# RobotCtrl_Core.net
KiCad netlist of a schematic drawn in Altium Designer
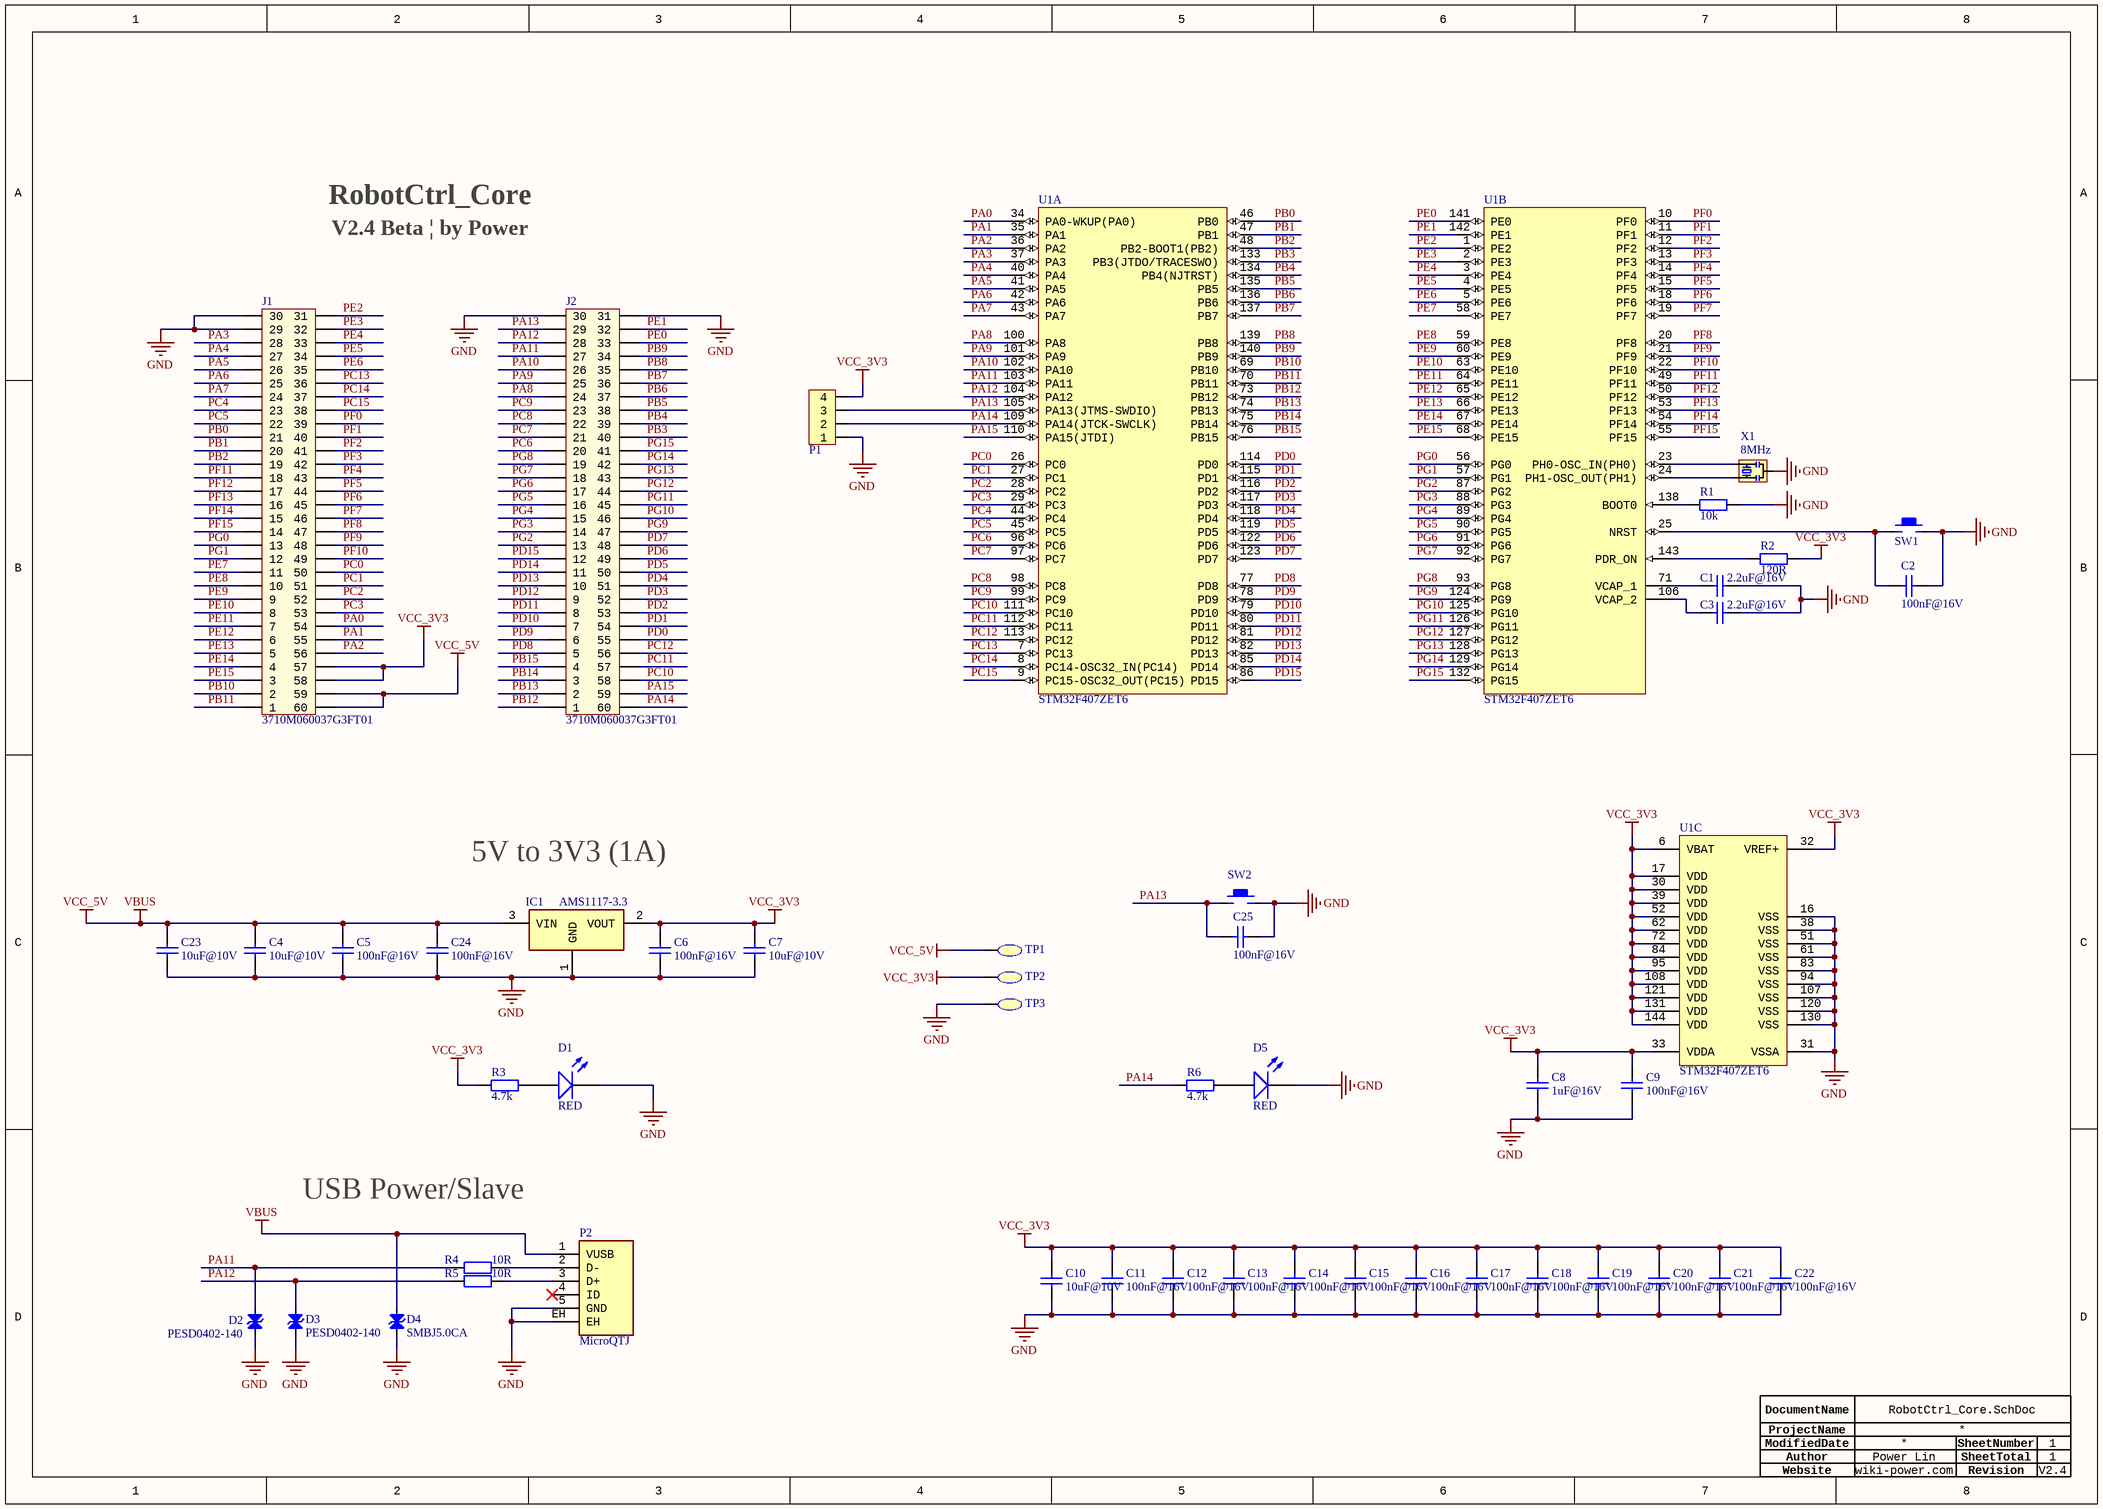
[diagram p0: RobotCtrl_Core.SchDoc]

(export (version "E")
  (design (tool "Eeschema 10.0.6"))
  (components
    (comp (ref "C1")
      (value "2.2uF@16V")
      (footprint "CAP-0402")
      (description "(CC0402KRX5R7BB225)")
      (libsource (lib "Power_Lib_Altium") (part "CAP"))
    )
    (comp (ref "C2")
      (value "100nF@16V")
      (footprint "CAP-0402")
      (description "(CC0402JRX7R7BB104)")
      (libsource (lib "Power_Lib_Altium") (part "CAP"))
    )
    (comp (ref "C3")
      (value "2.2uF@16V")
      (footprint "CAP-0402")
      (description "(CC0402KRX5R7BB225)")
      (libsource (lib "Power_Lib_Altium") (part "CAP"))
    )
    (comp (ref "C4")
      (value "10uF@10V")
      (footprint "CAP-0402")
      (description "(CC0402MRX5R6BB106)")
      (libsource (lib "Power_Lib_Altium") (part "CAP"))
    )
    (comp (ref "C5")
      (value "100nF@16V")
      (footprint "CAP-0402")
      (description "(CC0402JRX7R7BB104)")
      (libsource (lib "Power_Lib_Altium") (part "CAP"))
    )
    (comp (ref "C6")
      (value "100nF@16V")
      (footprint "CAP-0402")
      (description "(CC0402JRX7R7BB104)")
      (libsource (lib "Power_Lib_Altium") (part "CAP"))
    )
    (comp (ref "C7")
      (value "10uF@10V")
      (footprint "CAP-0402")
      (description "(CC0402MRX5R6BB106)")
      (libsource (lib "Power_Lib_Altium") (part "CAP"))
    )
    (comp (ref "C8")
      (value "1uF@16V")
      (footprint "CAP-0402")
      (description "(CC0402KRX5R7BB105)")
      (libsource (lib "Power_Lib_Altium") (part "CAP"))
    )
    (comp (ref "C9")
      (value "100nF@16V")
      (footprint "CAP-0402")
      (description "(CC0402JRX7R7BB104)")
      (libsource (lib "Power_Lib_Altium") (part "CAP"))
    )
    (comp (ref "C10")
      (value "10uF@10V")
      (footprint "CAP-0402")
      (description "(CC0402MRX5R6BB106)")
      (libsource (lib "Power_Lib_Altium") (part "CAP"))
    )
    (comp (ref "C11")
      (value "100nF@16V")
      (footprint "CAP-0402")
      (description "(CC0402JRX7R7BB104)")
      (libsource (lib "Power_Lib_Altium") (part "CAP"))
    )
    (comp (ref "C12")
      (value "100nF@16V")
      (footprint "CAP-0402")
      (description "(CC0402JRX7R7BB104)")
      (libsource (lib "Power_Lib_Altium") (part "CAP"))
    )
    (comp (ref "C13")
      (value "100nF@16V")
      (footprint "CAP-0402")
      (description "(CC0402JRX7R7BB104)")
      (libsource (lib "Power_Lib_Altium") (part "CAP"))
    )
    (comp (ref "C14")
      (value "100nF@16V")
      (footprint "CAP-0402")
      (description "(CC0402JRX7R7BB104)")
      (libsource (lib "Power_Lib_Altium") (part "CAP"))
    )
    (comp (ref "C15")
      (value "100nF@16V")
      (footprint "CAP-0402")
      (description "(CC0402JRX7R7BB104)")
      (libsource (lib "Power_Lib_Altium") (part "CAP"))
    )
    (comp (ref "C16")
      (value "100nF@16V")
      (footprint "CAP-0402")
      (description "(CC0402JRX7R7BB104)")
      (libsource (lib "Power_Lib_Altium") (part "CAP"))
    )
    (comp (ref "C17")
      (value "100nF@16V")
      (footprint "CAP-0402")
      (description "(CC0402JRX7R7BB104)")
      (libsource (lib "Power_Lib_Altium") (part "CAP"))
    )
    (comp (ref "C18")
      (value "100nF@16V")
      (footprint "CAP-0402")
      (description "(CC0402JRX7R7BB104)")
      (libsource (lib "Power_Lib_Altium") (part "CAP"))
    )
    (comp (ref "C19")
      (value "100nF@16V")
      (footprint "CAP-0402")
      (description "(CC0402JRX7R7BB104)")
      (libsource (lib "Power_Lib_Altium") (part "CAP"))
    )
    (comp (ref "C20")
      (value "100nF@16V")
      (footprint "CAP-0402")
      (description "(CC0402JRX7R7BB104)")
      (libsource (lib "Power_Lib_Altium") (part "CAP"))
    )
    (comp (ref "C21")
      (value "100nF@16V")
      (footprint "CAP-0402")
      (description "(CC0402JRX7R7BB104)")
      (libsource (lib "Power_Lib_Altium") (part "CAP"))
    )
    (comp (ref "C22")
      (value "100nF@16V")
      (footprint "CAP-0402")
      (description "(CC0402JRX7R7BB104)")
      (libsource (lib "Power_Lib_Altium") (part "CAP"))
    )
    (comp (ref "C23")
      (value "10uF@10V")
      (footprint "CAP-0402")
      (description "(CC0402MRX5R6BB106)")
      (libsource (lib "Power_Lib_Altium") (part "CAP"))
    )
    (comp (ref "C24")
      (value "100nF@16V")
      (footprint "CAP-0402")
      (description "(CC0402JRX7R7BB104)")
      (libsource (lib "Power_Lib_Altium") (part "CAP"))
    )
    (comp (ref "C25")
      (value "100nF@16V")
      (footprint "CAP-0402")
      (description "(CC0402JRX7R7BB104)")
      (libsource (lib "Power_Lib_Altium") (part "CAP"))
    )
    (comp (ref "D1")
      (value "RED")
      (footprint "LED-0402")
      (description "发光二极管")
      (libsource (lib "Power_Lib_Altium") (part "LED"))
    )
    (comp (ref "D2")
      (value "PESD0402-140")
      (footprint "D-0402")
      (libsource (lib "Power_Lib_Altium") (part "TVS_C"))
    )
    (comp (ref "D3")
      (value "PESD0402-140")
      (footprint "D-0402")
      (libsource (lib "Power_Lib_Altium") (part "TVS_C"))
    )
    (comp (ref "D4")
      (value "SMBJ5.0CA")
      (footprint "DO-214AA/SMB")
      (description "Brightking / MDD")
      (libsource (lib "Power_Lib_Altium") (part "TVS_C"))
    )
    (comp (ref "D5")
      (value "RED")
      (footprint "LED-0402")
      (description "发光二极管")
      (libsource (lib "Power_Lib_Altium") (part "LED"))
    )
    (comp (ref "IC1")
      (value "AMS1117-3.3")
      (footprint "SOT-223")
      (description "AMS1117-3.3 1.0A")
      (fields (field (name "MANUFACTURER_PART_NUMBER") "SI2302DS") (field (name "RS PART NUMBER") "7983053P"))
      (libsource (lib "Power_Lib_Altium") (part "AMS1117"))
    )
    (comp (ref "J1")
      (value "3710M060037G3FT01")
      (footprint "3710M060037G3FT01")
      (description "B2B Connector")
      (libsource (lib "Power_Lib_Altium") (part "3710M/F"))
    )
    (comp (ref "J2")
      (value "3710M060037G3FT01")
      (footprint "3710M060037G3FT01")
      (description "B2B Connector")
      (libsource (lib "Power_Lib_Altium") (part "3710M/F"))
    )
    (comp (ref "P1")
      (value "HDR1x4_2.54")
      (footprint "HDR1X4_2.54")
      (description "Header")
      (libsource (lib "Power_Lib_Altium") (part "HDR1x4_2.54"))
    )
    (comp (ref "P2")
      (value "MicroQTJ")
      (footprint "USB-MICRO")
      (description "USB_MICRO")
      (libsource (lib "Power_Lib_Altium") (part "USB_MICRO"))
    )
    (comp (ref "R1")
      (value "10k")
      (footprint "R-0402")
      (description "贴片电阻")
      (libsource (lib "") (part "RES_1"))
    )
    (comp (ref "R2")
      (value "120R")
      (footprint "R-0402")
      (description "贴片电阻")
      (libsource (lib "") (part "RES_1"))
    )
    (comp (ref "R3")
      (value "4.7k")
      (footprint "R-0402")
      (description "贴片电阻")
      (libsource (lib "") (part "RES_1"))
    )
    (comp (ref "R4")
      (value "10R")
      (footprint "R-0402")
      (description "贴片电阻")
      (libsource (lib "Power_Lib_Altium") (part "RES"))
    )
    (comp (ref "R5")
      (value "10R")
      (footprint "R-0402")
      (description "贴片电阻")
      (libsource (lib "Power_Lib_Altium") (part "RES"))
    )
    (comp (ref "R6")
      (value "4.7k")
      (footprint "R-0402")
      (description "贴片电阻")
      (libsource (lib "") (part "RES_1"))
    )
    (comp (ref "SW1")
      (value "KEY")
      (footprint "KEY-4P-4.2*3.4*2.5")
      (description "按键开关")
      (libsource (lib "Power_Lib_Altium") (part "KEY"))
    )
    (comp (ref "SW2")
      (value "KEY")
      (footprint "KEY-4P-4.2*3.4*2.5")
      (description "按键开关")
      (libsource (lib "Power_Lib_Altium") (part "KEY"))
    )
    (comp (ref "TP1")
      (value "TestPoint")
      (footprint "TestPoint")
      (description "测试点")
      (libsource (lib "Power_Lib_Altium") (part "TestPoint"))
    )
    (comp (ref "TP2")
      (value "TestPoint")
      (footprint "TestPoint")
      (description "测试点")
      (libsource (lib "Power_Lib_Altium") (part "TestPoint"))
    )
    (comp (ref "TP3")
      (value "TestPoint")
      (footprint "TestPoint")
      (description "测试点")
      (libsource (lib "Power_Lib_Altium") (part "TestPoint"))
    )
    (comp (ref "U1")
      (value "STM32F407ZET6")
      (footprint "STM-LQFP144_N")
      (fields (field (name "MANUFACTURER") "STMicroelectronics"))
      (libsource (lib "Power_Lib_Altium") (part "STM32F407ZET6"))
    )
    (comp (ref "X1")
      (value "8MHz")
      (footprint "SMD3213-3P")
      (description "CSTCE8M00G15C99-R0")
      (libsource (lib "Power_Lib_Altium") (part "XTAL"))
    )
  )
  (nets
    (net (code "1") (name "/PA0") (class "Default")
      (node (ref "J1") (pin "54") (pinfunction "54_54") (pintype "passive"))
      (node (ref "U1") (pin "34") (pinfunction "PA0-WKUP(PA0)_34") (pintype "bidirectional"))
    )
    (net (code "2") (name "/PA1") (class "Default")
      (node (ref "J1") (pin "55") (pinfunction "55_55") (pintype "passive"))
      (node (ref "U1") (pin "35") (pinfunction "PA1_35") (pintype "bidirectional"))
    )
    (net (code "3") (name "/PA2") (class "Default")
      (node (ref "J1") (pin "56") (pinfunction "56_56") (pintype "passive"))
      (node (ref "U1") (pin "36") (pinfunction "PA2_36") (pintype "bidirectional"))
    )
    (net (code "4") (name "/PA3") (class "Default")
      (node (ref "J1") (pin "28") (pinfunction "28_28") (pintype "passive"))
      (node (ref "U1") (pin "37") (pinfunction "PA3_37") (pintype "bidirectional"))
    )
    (net (code "5") (name "/PA4") (class "Default")
      (node (ref "J1") (pin "27") (pinfunction "27_27") (pintype "passive"))
      (node (ref "U1") (pin "40") (pinfunction "PA4_40") (pintype "bidirectional"))
    )
    (net (code "6") (name "/PA5") (class "Default")
      (node (ref "J1") (pin "26") (pinfunction "26_26") (pintype "passive"))
      (node (ref "U1") (pin "41") (pinfunction "PA5_41") (pintype "bidirectional"))
    )
    (net (code "7") (name "/PA6") (class "Default")
      (node (ref "J1") (pin "25") (pinfunction "25_25") (pintype "passive"))
      (node (ref "U1") (pin "42") (pinfunction "PA6_42") (pintype "bidirectional"))
    )
    (net (code "8") (name "/PA7") (class "Default")
      (node (ref "J1") (pin "24") (pinfunction "24_24") (pintype "passive"))
      (node (ref "U1") (pin "43") (pinfunction "PA7_43") (pintype "bidirectional"))
    )
    (net (code "9") (name "/PA8") (class "Default")
      (node (ref "J2") (pin "24") (pinfunction "24_24") (pintype "passive"))
      (node (ref "U1") (pin "100") (pinfunction "PA8_100") (pintype "bidirectional"))
    )
    (net (code "10") (name "/PA9") (class "Default")
      (node (ref "J2") (pin "25") (pinfunction "25_25") (pintype "passive"))
      (node (ref "U1") (pin "101") (pinfunction "PA9_101") (pintype "bidirectional"))
    )
    (net (code "11") (name "/PA10") (class "Default")
      (node (ref "J2") (pin "26") (pinfunction "26_26") (pintype "passive"))
      (node (ref "U1") (pin "102") (pinfunction "PA10_102") (pintype "bidirectional"))
    )
    (net (code "12") (name "/PA11") (class "Default")
      (node (ref "D2") (pin "2") (pinfunction "2_2") (pintype "passive"))
      (node (ref "J2") (pin "27") (pinfunction "27_27") (pintype "passive"))
      (node (ref "R4") (pin "1") (pinfunction "1_1") (pintype "passive"))
      (node (ref "U1") (pin "103") (pinfunction "PA11_103") (pintype "bidirectional"))
    )
    (net (code "13") (name "/PA12") (class "Default")
      (node (ref "D3") (pin "2") (pinfunction "2_2") (pintype "passive"))
      (node (ref "J2") (pin "28") (pinfunction "28_28") (pintype "passive"))
      (node (ref "R5") (pin "1") (pinfunction "1_1") (pintype "passive"))
      (node (ref "U1") (pin "104") (pinfunction "PA12_104") (pintype "bidirectional"))
    )
    (net (code "14") (name "/PA13") (class "Default")
      (node (ref "C25") (pin "2") (pinfunction "2_2") (pintype "passive"))
      (node (ref "J2") (pin "29") (pinfunction "29_29") (pintype "passive"))
      (node (ref "P1") (pin "3") (pinfunction "3_3") (pintype "passive"))
      (node (ref "SW2") (pin "1") (pinfunction "1_1") (pintype "passive"))
      (node (ref "U1") (pin "105") (pinfunction "PA13(JTMS-SWDIO)_105") (pintype "bidirectional"))
    )
    (net (code "15") (name "/PA14") (class "Default")
      (node (ref "J2") (pin "60") (pinfunction "60_60") (pintype "passive"))
      (node (ref "P1") (pin "2") (pinfunction "2_2") (pintype "passive"))
      (node (ref "R6") (pin "2") (pinfunction "2_2") (pintype "passive"))
      (node (ref "U1") (pin "109") (pinfunction "PA14(JTCK-SWCLK)_109") (pintype "bidirectional"))
    )
    (net (code "16") (name "/PA15") (class "Default")
      (node (ref "J2") (pin "59") (pinfunction "59_59") (pintype "passive"))
      (node (ref "U1") (pin "110") (pinfunction "PA15(JTDI)_110") (pintype "bidirectional"))
    )
    (net (code "17") (name "/PB0") (class "Default")
      (node (ref "J1") (pin "21") (pinfunction "21_21") (pintype "passive"))
      (node (ref "U1") (pin "46") (pinfunction "PB0_46") (pintype "bidirectional"))
    )
    (net (code "18") (name "/PB1") (class "Default")
      (node (ref "J1") (pin "20") (pinfunction "20_20") (pintype "passive"))
      (node (ref "U1") (pin "47") (pinfunction "PB1_47") (pintype "bidirectional"))
    )
    (net (code "19") (name "/PB2") (class "Default")
      (node (ref "J1") (pin "19") (pinfunction "19_19") (pintype "passive"))
      (node (ref "U1") (pin "48") (pinfunction "PB2-BOOT1(PB2)_48") (pintype "bidirectional"))
    )
    (net (code "20") (name "/PB3") (class "Default")
      (node (ref "J2") (pin "40") (pinfunction "40_40") (pintype "passive"))
      (node (ref "U1") (pin "133") (pinfunction "PB3(JTDO/TRACESWO)_133") (pintype "bidirectional"))
    )
    (net (code "21") (name "/PB4") (class "Default")
      (node (ref "J2") (pin "39") (pinfunction "39_39") (pintype "passive"))
      (node (ref "U1") (pin "134") (pinfunction "PB4(NJTRST)_134") (pintype "bidirectional"))
    )
    (net (code "22") (name "/PB5") (class "Default")
      (node (ref "J2") (pin "38") (pinfunction "38_38") (pintype "passive"))
      (node (ref "U1") (pin "135") (pinfunction "PB5_135") (pintype "bidirectional"))
    )
    (net (code "23") (name "/PB6") (class "Default")
      (node (ref "J2") (pin "37") (pinfunction "37_37") (pintype "passive"))
      (node (ref "U1") (pin "136") (pinfunction "PB6_136") (pintype "bidirectional"))
    )
    (net (code "24") (name "/PB7") (class "Default")
      (node (ref "J2") (pin "36") (pinfunction "36_36") (pintype "passive"))
      (node (ref "U1") (pin "137") (pinfunction "PB7_137") (pintype "bidirectional"))
    )
    (net (code "25") (name "/PB8") (class "Default")
      (node (ref "J2") (pin "35") (pinfunction "35_35") (pintype "passive"))
      (node (ref "U1") (pin "139") (pinfunction "PB8_139") (pintype "bidirectional"))
    )
    (net (code "26") (name "/PB9") (class "Default")
      (node (ref "J2") (pin "34") (pinfunction "34_34") (pintype "passive"))
      (node (ref "U1") (pin "140") (pinfunction "PB9_140") (pintype "bidirectional"))
    )
    (net (code "27") (name "/PB10") (class "Default")
      (node (ref "J1") (pin "2") (pinfunction "2_2") (pintype "passive"))
      (node (ref "U1") (pin "69") (pinfunction "PB10_69") (pintype "bidirectional"))
    )
    (net (code "28") (name "/PB11") (class "Default")
      (node (ref "J1") (pin "1") (pinfunction "1_1") (pintype "passive"))
      (node (ref "U1") (pin "70") (pinfunction "PB11_70") (pintype "bidirectional"))
    )
    (net (code "29") (name "/PB12") (class "Default")
      (node (ref "J2") (pin "1") (pinfunction "1_1") (pintype "passive"))
      (node (ref "U1") (pin "73") (pinfunction "PB12_73") (pintype "bidirectional"))
    )
    (net (code "30") (name "/PB13") (class "Default")
      (node (ref "J2") (pin "2") (pinfunction "2_2") (pintype "passive"))
      (node (ref "U1") (pin "74") (pinfunction "PB13_74") (pintype "bidirectional"))
    )
    (net (code "31") (name "/PB14") (class "Default")
      (node (ref "J2") (pin "3") (pinfunction "3_3") (pintype "passive"))
      (node (ref "U1") (pin "75") (pinfunction "PB14_75") (pintype "bidirectional"))
    )
    (net (code "32") (name "/PB15") (class "Default")
      (node (ref "J2") (pin "4") (pinfunction "4_4") (pintype "passive"))
      (node (ref "U1") (pin "76") (pinfunction "PB15_76") (pintype "bidirectional"))
    )
    (net (code "33") (name "/PC0") (class "Default")
      (node (ref "J1") (pin "50") (pinfunction "50_50") (pintype "passive"))
      (node (ref "U1") (pin "26") (pinfunction "PC0_26") (pintype "bidirectional"))
    )
    (net (code "34") (name "/PC1") (class "Default")
      (node (ref "J1") (pin "51") (pinfunction "51_51") (pintype "passive"))
      (node (ref "U1") (pin "27") (pinfunction "PC1_27") (pintype "bidirectional"))
    )
    (net (code "35") (name "/PC2") (class "Default")
      (node (ref "J1") (pin "52") (pinfunction "52_52") (pintype "passive"))
      (node (ref "U1") (pin "28") (pinfunction "PC2_28") (pintype "bidirectional"))
    )
    (net (code "36") (name "/PC3") (class "Default")
      (node (ref "J1") (pin "53") (pinfunction "53_53") (pintype "passive"))
      (node (ref "U1") (pin "29") (pinfunction "PC3_29") (pintype "bidirectional"))
    )
    (net (code "37") (name "/PC4") (class "Default")
      (node (ref "J1") (pin "23") (pinfunction "23_23") (pintype "passive"))
      (node (ref "U1") (pin "44") (pinfunction "PC4_44") (pintype "bidirectional"))
    )
    (net (code "38") (name "/PC5") (class "Default")
      (node (ref "J1") (pin "22") (pinfunction "22_22") (pintype "passive"))
      (node (ref "U1") (pin "45") (pinfunction "PC5_45") (pintype "bidirectional"))
    )
    (net (code "39") (name "/PC6") (class "Default")
      (node (ref "J2") (pin "20") (pinfunction "20_20") (pintype "passive"))
      (node (ref "U1") (pin "96") (pinfunction "PC6_96") (pintype "bidirectional"))
    )
    (net (code "40") (name "/PC7") (class "Default")
      (node (ref "J2") (pin "21") (pinfunction "21_21") (pintype "passive"))
      (node (ref "U1") (pin "97") (pinfunction "PC7_97") (pintype "bidirectional"))
    )
    (net (code "41") (name "/PC8") (class "Default")
      (node (ref "J2") (pin "22") (pinfunction "22_22") (pintype "passive"))
      (node (ref "U1") (pin "98") (pinfunction "PC8_98") (pintype "bidirectional"))
    )
    (net (code "42") (name "/PC9") (class "Default")
      (node (ref "J2") (pin "23") (pinfunction "23_23") (pintype "passive"))
      (node (ref "U1") (pin "99") (pinfunction "PC9_99") (pintype "bidirectional"))
    )
    (net (code "43") (name "/PC10") (class "Default")
      (node (ref "J2") (pin "58") (pinfunction "58_58") (pintype "passive"))
      (node (ref "U1") (pin "111") (pinfunction "PC10_111") (pintype "bidirectional"))
    )
    (net (code "44") (name "/PC11") (class "Default")
      (node (ref "J2") (pin "57") (pinfunction "57_57") (pintype "passive"))
      (node (ref "U1") (pin "112") (pinfunction "PC11_112") (pintype "bidirectional"))
    )
    (net (code "45") (name "/PC12") (class "Default")
      (node (ref "J2") (pin "56") (pinfunction "56_56") (pintype "passive"))
      (node (ref "U1") (pin "113") (pinfunction "PC12_113") (pintype "bidirectional"))
    )
    (net (code "46") (name "/PC13") (class "Default")
      (node (ref "J1") (pin "36") (pinfunction "36_36") (pintype "passive"))
      (node (ref "U1") (pin "7") (pinfunction "PC13_7") (pintype "bidirectional"))
    )
    (net (code "47") (name "/PC14") (class "Default")
      (node (ref "J1") (pin "37") (pinfunction "37_37") (pintype "passive"))
      (node (ref "U1") (pin "8") (pinfunction "PC14-OSC32_IN(PC14)_8") (pintype "bidirectional"))
    )
    (net (code "48") (name "/PC15") (class "Default")
      (node (ref "J1") (pin "38") (pinfunction "38_38") (pintype "passive"))
      (node (ref "U1") (pin "9") (pinfunction "PC15-OSC32_OUT(PC15)_9") (pintype "bidirectional"))
    )
    (net (code "49") (name "/PD0") (class "Default")
      (node (ref "J2") (pin "55") (pinfunction "55_55") (pintype "passive"))
      (node (ref "U1") (pin "114") (pinfunction "PD0_114") (pintype "bidirectional"))
    )
    (net (code "50") (name "/PD1") (class "Default")
      (node (ref "J2") (pin "54") (pinfunction "54_54") (pintype "passive"))
      (node (ref "U1") (pin "115") (pinfunction "PD1_115") (pintype "bidirectional"))
    )
    (net (code "51") (name "/PD2") (class "Default")
      (node (ref "J2") (pin "53") (pinfunction "53_53") (pintype "passive"))
      (node (ref "U1") (pin "116") (pinfunction "PD2_116") (pintype "bidirectional"))
    )
    (net (code "52") (name "/PD3") (class "Default")
      (node (ref "J2") (pin "52") (pinfunction "52_52") (pintype "passive"))
      (node (ref "U1") (pin "117") (pinfunction "PD3_117") (pintype "bidirectional"))
    )
    (net (code "53") (name "/PD4") (class "Default")
      (node (ref "J2") (pin "51") (pinfunction "51_51") (pintype "passive"))
      (node (ref "U1") (pin "118") (pinfunction "PD4_118") (pintype "bidirectional"))
    )
    (net (code "54") (name "/PD5") (class "Default")
      (node (ref "J2") (pin "50") (pinfunction "50_50") (pintype "passive"))
      (node (ref "U1") (pin "119") (pinfunction "PD5_119") (pintype "bidirectional"))
    )
    (net (code "55") (name "/PD6") (class "Default")
      (node (ref "J2") (pin "49") (pinfunction "49_49") (pintype "passive"))
      (node (ref "U1") (pin "122") (pinfunction "PD6_122") (pintype "bidirectional"))
    )
    (net (code "56") (name "/PD7") (class "Default")
      (node (ref "J2") (pin "48") (pinfunction "48_48") (pintype "passive"))
      (node (ref "U1") (pin "123") (pinfunction "PD7_123") (pintype "bidirectional"))
    )
    (net (code "57") (name "/PD8") (class "Default")
      (node (ref "J2") (pin "5") (pinfunction "5_5") (pintype "passive"))
      (node (ref "U1") (pin "77") (pinfunction "PD8_77") (pintype "bidirectional"))
    )
    (net (code "58") (name "/PD9") (class "Default")
      (node (ref "J2") (pin "6") (pinfunction "6_6") (pintype "passive"))
      (node (ref "U1") (pin "78") (pinfunction "PD9_78") (pintype "bidirectional"))
    )
    (net (code "59") (name "/PD10") (class "Default")
      (node (ref "J2") (pin "7") (pinfunction "7_7") (pintype "passive"))
      (node (ref "U1") (pin "79") (pinfunction "PD10_79") (pintype "bidirectional"))
    )
    (net (code "60") (name "/PD11") (class "Default")
      (node (ref "J2") (pin "8") (pinfunction "8_8") (pintype "passive"))
      (node (ref "U1") (pin "80") (pinfunction "PD11_80") (pintype "bidirectional"))
    )
    (net (code "61") (name "/PD12") (class "Default")
      (node (ref "J2") (pin "9") (pinfunction "9_9") (pintype "passive"))
      (node (ref "U1") (pin "81") (pinfunction "PD12_81") (pintype "bidirectional"))
    )
    (net (code "62") (name "/PD13") (class "Default")
      (node (ref "J2") (pin "10") (pinfunction "10_10") (pintype "passive"))
      (node (ref "U1") (pin "82") (pinfunction "PD13_82") (pintype "bidirectional"))
    )
    (net (code "63") (name "/PD14") (class "Default")
      (node (ref "J2") (pin "11") (pinfunction "11_11") (pintype "passive"))
      (node (ref "U1") (pin "85") (pinfunction "PD14_85") (pintype "bidirectional"))
    )
    (net (code "64") (name "/PD15") (class "Default")
      (node (ref "J2") (pin "12") (pinfunction "12_12") (pintype "passive"))
      (node (ref "U1") (pin "86") (pinfunction "PD15_86") (pintype "bidirectional"))
    )
    (net (code "65") (name "/PE0") (class "Default")
      (node (ref "J2") (pin "33") (pinfunction "33_33") (pintype "passive"))
      (node (ref "U1") (pin "141") (pinfunction "PE0_141") (pintype "bidirectional"))
    )
    (net (code "66") (name "/PE1") (class "Default")
      (node (ref "J2") (pin "32") (pinfunction "32_32") (pintype "passive"))
      (node (ref "U1") (pin "142") (pinfunction "PE1_142") (pintype "bidirectional"))
    )
    (net (code "67") (name "/PE2") (class "Default")
      (node (ref "J1") (pin "31") (pinfunction "31_31") (pintype "passive"))
      (node (ref "U1") (pin "1") (pinfunction "PE2_1") (pintype "bidirectional"))
    )
    (net (code "68") (name "/PE3") (class "Default")
      (node (ref "J1") (pin "32") (pinfunction "32_32") (pintype "passive"))
      (node (ref "U1") (pin "2") (pinfunction "PE3_2") (pintype "bidirectional"))
    )
    (net (code "69") (name "/PE4") (class "Default")
      (node (ref "J1") (pin "33") (pinfunction "33_33") (pintype "passive"))
      (node (ref "U1") (pin "3") (pinfunction "PE4_3") (pintype "bidirectional"))
    )
    (net (code "70") (name "/PE5") (class "Default")
      (node (ref "J1") (pin "34") (pinfunction "34_34") (pintype "passive"))
      (node (ref "U1") (pin "4") (pinfunction "PE5_4") (pintype "bidirectional"))
    )
    (net (code "71") (name "/PE6") (class "Default")
      (node (ref "J1") (pin "35") (pinfunction "35_35") (pintype "passive"))
      (node (ref "U1") (pin "5") (pinfunction "PE6_5") (pintype "bidirectional"))
    )
    (net (code "72") (name "/PE7") (class "Default")
      (node (ref "J1") (pin "11") (pinfunction "11_11") (pintype "passive"))
      (node (ref "U1") (pin "58") (pinfunction "PE7_58") (pintype "bidirectional"))
    )
    (net (code "73") (name "/PE8") (class "Default")
      (node (ref "J1") (pin "10") (pinfunction "10_10") (pintype "passive"))
      (node (ref "U1") (pin "59") (pinfunction "PE8_59") (pintype "bidirectional"))
    )
    (net (code "74") (name "/PE9") (class "Default")
      (node (ref "J1") (pin "9") (pinfunction "9_9") (pintype "passive"))
      (node (ref "U1") (pin "60") (pinfunction "PE9_60") (pintype "bidirectional"))
    )
    (net (code "75") (name "/PE10") (class "Default")
      (node (ref "J1") (pin "8") (pinfunction "8_8") (pintype "passive"))
      (node (ref "U1") (pin "63") (pinfunction "PE10_63") (pintype "bidirectional"))
    )
    (net (code "76") (name "/PE11") (class "Default")
      (node (ref "J1") (pin "7") (pinfunction "7_7") (pintype "passive"))
      (node (ref "U1") (pin "64") (pinfunction "PE11_64") (pintype "bidirectional"))
    )
    (net (code "77") (name "/PE12") (class "Default")
      (node (ref "J1") (pin "6") (pinfunction "6_6") (pintype "passive"))
      (node (ref "U1") (pin "65") (pinfunction "PE12_65") (pintype "bidirectional"))
    )
    (net (code "78") (name "/PE13") (class "Default")
      (node (ref "J1") (pin "5") (pinfunction "5_5") (pintype "passive"))
      (node (ref "U1") (pin "66") (pinfunction "PE13_66") (pintype "bidirectional"))
    )
    (net (code "79") (name "/PE14") (class "Default")
      (node (ref "J1") (pin "4") (pinfunction "4_4") (pintype "passive"))
      (node (ref "U1") (pin "67") (pinfunction "PE14_67") (pintype "bidirectional"))
    )
    (net (code "80") (name "/PE15") (class "Default")
      (node (ref "J1") (pin "3") (pinfunction "3_3") (pintype "passive"))
      (node (ref "U1") (pin "68") (pinfunction "PE15_68") (pintype "bidirectional"))
    )
    (net (code "81") (name "/PF0") (class "Default")
      (node (ref "J1") (pin "39") (pinfunction "39_39") (pintype "passive"))
      (node (ref "U1") (pin "10") (pinfunction "PF0_10") (pintype "bidirectional"))
    )
    (net (code "82") (name "/PF1") (class "Default")
      (node (ref "J1") (pin "40") (pinfunction "40_40") (pintype "passive"))
      (node (ref "U1") (pin "11") (pinfunction "PF1_11") (pintype "bidirectional"))
    )
    (net (code "83") (name "/PF2") (class "Default")
      (node (ref "J1") (pin "41") (pinfunction "41_41") (pintype "passive"))
      (node (ref "U1") (pin "12") (pinfunction "PF2_12") (pintype "bidirectional"))
    )
    (net (code "84") (name "/PF3") (class "Default")
      (node (ref "J1") (pin "42") (pinfunction "42_42") (pintype "passive"))
      (node (ref "U1") (pin "13") (pinfunction "PF3_13") (pintype "bidirectional"))
    )
    (net (code "85") (name "/PF4") (class "Default")
      (node (ref "J1") (pin "43") (pinfunction "43_43") (pintype "passive"))
      (node (ref "U1") (pin "14") (pinfunction "PF4_14") (pintype "bidirectional"))
    )
    (net (code "86") (name "/PF5") (class "Default")
      (node (ref "J1") (pin "44") (pinfunction "44_44") (pintype "passive"))
      (node (ref "U1") (pin "15") (pinfunction "PF5_15") (pintype "bidirectional"))
    )
    (net (code "87") (name "/PF6") (class "Default")
      (node (ref "J1") (pin "45") (pinfunction "45_45") (pintype "passive"))
      (node (ref "U1") (pin "18") (pinfunction "PF6_18") (pintype "bidirectional"))
    )
    (net (code "88") (name "/PF7") (class "Default")
      (node (ref "J1") (pin "46") (pinfunction "46_46") (pintype "passive"))
      (node (ref "U1") (pin "19") (pinfunction "PF7_19") (pintype "bidirectional"))
    )
    (net (code "89") (name "/PF8") (class "Default")
      (node (ref "J1") (pin "47") (pinfunction "47_47") (pintype "passive"))
      (node (ref "U1") (pin "20") (pinfunction "PF8_20") (pintype "bidirectional"))
    )
    (net (code "90") (name "/PF9") (class "Default")
      (node (ref "J1") (pin "48") (pinfunction "48_48") (pintype "passive"))
      (node (ref "U1") (pin "21") (pinfunction "PF9_21") (pintype "bidirectional"))
    )
    (net (code "91") (name "/PF10") (class "Default")
      (node (ref "J1") (pin "49") (pinfunction "49_49") (pintype "passive"))
      (node (ref "U1") (pin "22") (pinfunction "PF10_22") (pintype "bidirectional"))
    )
    (net (code "92") (name "/PF11") (class "Default")
      (node (ref "J1") (pin "18") (pinfunction "18_18") (pintype "passive"))
      (node (ref "U1") (pin "49") (pinfunction "PF11_49") (pintype "bidirectional"))
    )
    (net (code "93") (name "/PF12") (class "Default")
      (node (ref "J1") (pin "17") (pinfunction "17_17") (pintype "passive"))
      (node (ref "U1") (pin "50") (pinfunction "PF12_50") (pintype "bidirectional"))
    )
    (net (code "94") (name "/PF13") (class "Default")
      (node (ref "J1") (pin "16") (pinfunction "16_16") (pintype "passive"))
      (node (ref "U1") (pin "53") (pinfunction "PF13_53") (pintype "bidirectional"))
    )
    (net (code "95") (name "/PF14") (class "Default")
      (node (ref "J1") (pin "15") (pinfunction "15_15") (pintype "passive"))
      (node (ref "U1") (pin "54") (pinfunction "PF14_54") (pintype "bidirectional"))
    )
    (net (code "96") (name "/PF15") (class "Default")
      (node (ref "J1") (pin "14") (pinfunction "14_14") (pintype "passive"))
      (node (ref "U1") (pin "55") (pinfunction "PF15_55") (pintype "bidirectional"))
    )
    (net (code "97") (name "/PG0") (class "Default")
      (node (ref "J1") (pin "13") (pinfunction "13_13") (pintype "passive"))
      (node (ref "U1") (pin "56") (pinfunction "PG0_56") (pintype "bidirectional"))
    )
    (net (code "98") (name "/PG1") (class "Default")
      (node (ref "J1") (pin "12") (pinfunction "12_12") (pintype "passive"))
      (node (ref "U1") (pin "57") (pinfunction "PG1_57") (pintype "bidirectional"))
    )
    (net (code "99") (name "/PG2") (class "Default")
      (node (ref "J2") (pin "13") (pinfunction "13_13") (pintype "passive"))
      (node (ref "U1") (pin "87") (pinfunction "PG2_87") (pintype "bidirectional"))
    )
    (net (code "100") (name "/PG3") (class "Default")
      (node (ref "J2") (pin "14") (pinfunction "14_14") (pintype "passive"))
      (node (ref "U1") (pin "88") (pinfunction "PG3_88") (pintype "bidirectional"))
    )
    (net (code "101") (name "/PG4") (class "Default")
      (node (ref "J2") (pin "15") (pinfunction "15_15") (pintype "passive"))
      (node (ref "U1") (pin "89") (pinfunction "PG4_89") (pintype "bidirectional"))
    )
    (net (code "102") (name "/PG5") (class "Default")
      (node (ref "J2") (pin "16") (pinfunction "16_16") (pintype "passive"))
      (node (ref "U1") (pin "90") (pinfunction "PG5_90") (pintype "bidirectional"))
    )
    (net (code "103") (name "/PG6") (class "Default")
      (node (ref "J2") (pin "17") (pinfunction "17_17") (pintype "passive"))
      (node (ref "U1") (pin "91") (pinfunction "PG6_91") (pintype "bidirectional"))
    )
    (net (code "104") (name "/PG7") (class "Default")
      (node (ref "J2") (pin "18") (pinfunction "18_18") (pintype "passive"))
      (node (ref "U1") (pin "92") (pinfunction "PG7_92") (pintype "bidirectional"))
    )
    (net (code "105") (name "/PG8") (class "Default")
      (node (ref "J2") (pin "19") (pinfunction "19_19") (pintype "passive"))
      (node (ref "U1") (pin "93") (pinfunction "PG8_93") (pintype "bidirectional"))
    )
    (net (code "106") (name "/PG9") (class "Default")
      (node (ref "J2") (pin "47") (pinfunction "47_47") (pintype "passive"))
      (node (ref "U1") (pin "124") (pinfunction "PG9_124") (pintype "bidirectional"))
    )
    (net (code "107") (name "/PG10") (class "Default")
      (node (ref "J2") (pin "46") (pinfunction "46_46") (pintype "passive"))
      (node (ref "U1") (pin "125") (pinfunction "PG10_125") (pintype "bidirectional"))
    )
    (net (code "108") (name "/PG11") (class "Default")
      (node (ref "J2") (pin "45") (pinfunction "45_45") (pintype "passive"))
      (node (ref "U1") (pin "126") (pinfunction "PG11_126") (pintype "bidirectional"))
    )
    (net (code "109") (name "/PG12") (class "Default")
      (node (ref "J2") (pin "44") (pinfunction "44_44") (pintype "passive"))
      (node (ref "U1") (pin "127") (pinfunction "PG12_127") (pintype "bidirectional"))
    )
    (net (code "110") (name "/PG13") (class "Default")
      (node (ref "J2") (pin "43") (pinfunction "43_43") (pintype "passive"))
      (node (ref "U1") (pin "128") (pinfunction "PG13_128") (pintype "bidirectional"))
    )
    (net (code "111") (name "/PG14") (class "Default")
      (node (ref "J2") (pin "42") (pinfunction "42_42") (pintype "passive"))
      (node (ref "U1") (pin "129") (pinfunction "PG14_129") (pintype "bidirectional"))
    )
    (net (code "112") (name "/PG15") (class "Default")
      (node (ref "J2") (pin "41") (pinfunction "41_41") (pintype "passive"))
      (node (ref "U1") (pin "132") (pinfunction "PG15_132") (pintype "bidirectional"))
    )
    (net (code "113") (name "GND") (class "Default")
      (node (ref "C1") (pin "1") (pinfunction "1_1") (pintype "passive"))
      (node (ref "C10") (pin "1") (pinfunction "1_1") (pintype "passive"))
      (node (ref "C11") (pin "1") (pinfunction "1_1") (pintype "passive"))
      (node (ref "C12") (pin "1") (pinfunction "1_1") (pintype "passive"))
      (node (ref "C13") (pin "1") (pinfunction "1_1") (pintype "passive"))
      (node (ref "C14") (pin "1") (pinfunction "1_1") (pintype "passive"))
      (node (ref "C15") (pin "1") (pinfunction "1_1") (pintype "passive"))
      (node (ref "C16") (pin "1") (pinfunction "1_1") (pintype "passive"))
      (node (ref "C17") (pin "1") (pinfunction "1_1") (pintype "passive"))
      (node (ref "C18") (pin "1") (pinfunction "1_1") (pintype "passive"))
      (node (ref "C19") (pin "1") (pinfunction "1_1") (pintype "passive"))
      (node (ref "C2") (pin "1") (pinfunction "1_1") (pintype "passive"))
      (node (ref "C20") (pin "1") (pinfunction "1_1") (pintype "passive"))
      (node (ref "C21") (pin "1") (pinfunction "1_1") (pintype "passive"))
      (node (ref "C22") (pin "1") (pinfunction "1_1") (pintype "passive"))
      (node (ref "C23") (pin "1") (pinfunction "1_1") (pintype "passive"))
      (node (ref "C24") (pin "1") (pinfunction "1_1") (pintype "passive"))
      (node (ref "C25") (pin "1") (pinfunction "1_1") (pintype "passive"))
      (node (ref "C3") (pin "1") (pinfunction "1_1") (pintype "passive"))
      (node (ref "C4") (pin "1") (pinfunction "1_1") (pintype "passive"))
      (node (ref "C5") (pin "1") (pinfunction "1_1") (pintype "passive"))
      (node (ref "C6") (pin "1") (pinfunction "1_1") (pintype "passive"))
      (node (ref "C7") (pin "1") (pinfunction "1_1") (pintype "passive"))
      (node (ref "C8") (pin "1") (pinfunction "1_1") (pintype "passive"))
      (node (ref "C9") (pin "1") (pinfunction "1_1") (pintype "passive"))
      (node (ref "D1") (pin "K") (pinfunction "K_K") (pintype "passive"))
      (node (ref "D2") (pin "1") (pinfunction "1_1") (pintype "passive"))
      (node (ref "D3") (pin "1") (pinfunction "1_1") (pintype "passive"))
      (node (ref "D4") (pin "1") (pinfunction "1_1") (pintype "passive"))
      (node (ref "D5") (pin "K") (pinfunction "K_K") (pintype "passive"))
      (node (ref "IC1") (pin "1") (pinfunction "GND_1") (pintype "passive"))
      (node (ref "J1") (pin "29") (pinfunction "29_29") (pintype "passive"))
      (node (ref "J1") (pin "30") (pinfunction "30_30") (pintype "passive"))
      (node (ref "J2") (pin "30") (pinfunction "30_30") (pintype "passive"))
      (node (ref "J2") (pin "31") (pinfunction "31_31") (pintype "passive"))
      (node (ref "P1") (pin "1") (pinfunction "1_1") (pintype "passive"))
      (node (ref "P2") (pin "5") (pinfunction "GND_5") (pintype "passive"))
      (node (ref "P2") (pin "EH") (pinfunction "EH_EH") (pintype "passive"))
      (node (ref "R1") (pin "1") (pinfunction "1_1") (pintype "passive"))
      (node (ref "SW1") (pin "2") (pinfunction "2_2") (pintype "passive"))
      (node (ref "SW2") (pin "2") (pinfunction "2_2") (pintype "passive"))
      (node (ref "TP3") (pin "1") (pinfunction "1_1") (pintype "passive"))
      (node (ref "U1") (pin "107") (pinfunction "VSS_107") (pintype "power_in"))
      (node (ref "U1") (pin "120") (pinfunction "VSS_120") (pintype "power_in"))
      (node (ref "U1") (pin "130") (pinfunction "VSS_130") (pintype "power_in"))
      (node (ref "U1") (pin "16") (pinfunction "VSS_16") (pintype "power_in"))
      (node (ref "U1") (pin "31") (pinfunction "VSSA_31") (pintype "power_in"))
      (node (ref "U1") (pin "38") (pinfunction "VSS_38") (pintype "power_in"))
      (node (ref "U1") (pin "51") (pinfunction "VSS_51") (pintype "power_in"))
      (node (ref "U1") (pin "61") (pinfunction "VSS_61") (pintype "power_in"))
      (node (ref "U1") (pin "83") (pinfunction "VSS_83") (pintype "power_in"))
      (node (ref "U1") (pin "94") (pinfunction "VSS_94") (pintype "power_in"))
      (node (ref "X1") (pin "2") (pinfunction "GND_2") (pintype "passive"))
    )
    (net (code "114") (name "Net-(D1-PadA)") (class "Default")
      (node (ref "D1") (pin "A") (pinfunction "A_A") (pintype "passive"))
      (node (ref "R3") (pin "1") (pinfunction "1_1") (pintype "passive"))
    )
    (net (code "115") (name "Net-(D5-PadA)") (class "Default")
      (node (ref "D5") (pin "A") (pinfunction "A_A") (pintype "passive"))
      (node (ref "R6") (pin "1") (pinfunction "1_1") (pintype "passive"))
    )
    (net (code "116") (name "Net-(P2-D+)") (class "Default")
      (node (ref "P2") (pin "3") (pinfunction "D+_3") (pintype "passive"))
      (node (ref "R5") (pin "2") (pinfunction "2_2") (pintype "passive"))
    )
    (net (code "117") (name "Net-(P2-D-)") (class "Default")
      (node (ref "P2") (pin "2") (pinfunction "D-_2") (pintype "passive"))
      (node (ref "R4") (pin "2") (pinfunction "2_2") (pintype "passive"))
    )
    (net (code "118") (name "Net-(U1B-BOOT0)") (class "Default")
      (node (ref "R1") (pin "2") (pinfunction "2_2") (pintype "passive"))
      (node (ref "U1") (pin "138") (pinfunction "BOOT0_138") (pintype "input"))
    )
    (net (code "119") (name "Net-(U1B-NRST)") (class "Default")
      (node (ref "C2") (pin "2") (pinfunction "2_2") (pintype "passive"))
      (node (ref "SW1") (pin "1") (pinfunction "1_1") (pintype "passive"))
      (node (ref "U1") (pin "25") (pinfunction "NRST_25") (pintype "bidirectional"))
    )
    (net (code "120") (name "Net-(U1B-PDR_ON)") (class "Default")
      (node (ref "R2") (pin "2") (pinfunction "2_2") (pintype "passive"))
      (node (ref "U1") (pin "143") (pinfunction "PDR_ON_143") (pintype "input"))
    )
    (net (code "121") (name "Net-(U1B-PH0-OSC_IN(PH0))") (class "Default")
      (node (ref "U1") (pin "23") (pinfunction "PH0-OSC_IN(PH0)_23") (pintype "bidirectional"))
      (node (ref "X1") (pin "3") (pinfunction "OSC2_3") (pintype "passive"))
    )
    (net (code "122") (name "Net-(U1B-PH1-OSC_OUT(PH1))") (class "Default")
      (node (ref "U1") (pin "24") (pinfunction "PH1-OSC_OUT(PH1)_24") (pintype "bidirectional"))
      (node (ref "X1") (pin "1") (pinfunction "OSC1_1") (pintype "passive"))
    )
    (net (code "123") (name "Net-(U1B-VCAP_1)") (class "Default")
      (node (ref "C1") (pin "2") (pinfunction "2_2") (pintype "passive"))
      (node (ref "U1") (pin "71") (pinfunction "VCAP_1_71") (pintype "power_in"))
    )
    (net (code "124") (name "Net-(U1B-VCAP_2)") (class "Default")
      (node (ref "C3") (pin "2") (pinfunction "2_2") (pintype "passive"))
      (node (ref "U1") (pin "106") (pinfunction "VCAP_2_106") (pintype "power_in"))
    )
    (net (code "125") (name "VBUS") (class "Default")
      (node (ref "C23") (pin "2") (pinfunction "2_2") (pintype "passive"))
      (node (ref "C24") (pin "2") (pinfunction "2_2") (pintype "passive"))
      (node (ref "C4") (pin "2") (pinfunction "2_2") (pintype "passive"))
      (node (ref "C5") (pin "2") (pinfunction "2_2") (pintype "passive"))
      (node (ref "D4") (pin "2") (pinfunction "2_2") (pintype "passive"))
      (node (ref "IC1") (pin "3") (pinfunction "VIN_3") (pintype "passive"))
      (node (ref "J1") (pin "59") (pinfunction "59_59") (pintype "passive"))
      (node (ref "J1") (pin "60") (pinfunction "60_60") (pintype "passive"))
      (node (ref "P2") (pin "1") (pinfunction "VUSB_1") (pintype "passive"))
      (node (ref "TP1") (pin "1") (pinfunction "1_1") (pintype "passive"))
    )
    (net (code "126") (name "VCC_3V3") (class "Default")
      (node (ref "C10") (pin "2") (pinfunction "2_2") (pintype "passive"))
      (node (ref "C11") (pin "2") (pinfunction "2_2") (pintype "passive"))
      (node (ref "C12") (pin "2") (pinfunction "2_2") (pintype "passive"))
      (node (ref "C13") (pin "2") (pinfunction "2_2") (pintype "passive"))
      (node (ref "C14") (pin "2") (pinfunction "2_2") (pintype "passive"))
      (node (ref "C15") (pin "2") (pinfunction "2_2") (pintype "passive"))
      (node (ref "C16") (pin "2") (pinfunction "2_2") (pintype "passive"))
      (node (ref "C17") (pin "2") (pinfunction "2_2") (pintype "passive"))
      (node (ref "C18") (pin "2") (pinfunction "2_2") (pintype "passive"))
      (node (ref "C19") (pin "2") (pinfunction "2_2") (pintype "passive"))
      (node (ref "C20") (pin "2") (pinfunction "2_2") (pintype "passive"))
      (node (ref "C21") (pin "2") (pinfunction "2_2") (pintype "passive"))
      (node (ref "C22") (pin "2") (pinfunction "2_2") (pintype "passive"))
      (node (ref "C6") (pin "2") (pinfunction "2_2") (pintype "passive"))
      (node (ref "C7") (pin "2") (pinfunction "2_2") (pintype "passive"))
      (node (ref "C8") (pin "2") (pinfunction "2_2") (pintype "passive"))
      (node (ref "C9") (pin "2") (pinfunction "2_2") (pintype "passive"))
      (node (ref "IC1") (pin "2") (pinfunction "VOUT_2") (pintype "passive"))
      (node (ref "J1") (pin "57") (pinfunction "57_57") (pintype "passive"))
      (node (ref "J1") (pin "58") (pinfunction "58_58") (pintype "passive"))
      (node (ref "P1") (pin "4") (pinfunction "4_4") (pintype "passive"))
      (node (ref "R2") (pin "1") (pinfunction "1_1") (pintype "passive"))
      (node (ref "R3") (pin "2") (pinfunction "2_2") (pintype "passive"))
      (node (ref "TP2") (pin "1") (pinfunction "1_1") (pintype "passive"))
      (node (ref "U1") (pin "108") (pinfunction "VDD_108") (pintype "power_in"))
      (node (ref "U1") (pin "121") (pinfunction "VDD_121") (pintype "power_in"))
      (node (ref "U1") (pin "131") (pinfunction "VDD_131") (pintype "power_in"))
      (node (ref "U1") (pin "144") (pinfunction "VDD_144") (pintype "power_in"))
      (node (ref "U1") (pin "17") (pinfunction "VDD_17") (pintype "power_in"))
      (node (ref "U1") (pin "30") (pinfunction "VDD_30") (pintype "power_in"))
      (node (ref "U1") (pin "32") (pinfunction "VREF+_32") (pintype "power_in"))
      (node (ref "U1") (pin "33") (pinfunction "VDDA_33") (pintype "power_in"))
      (node (ref "U1") (pin "39") (pinfunction "VDD_39") (pintype "power_in"))
      (node (ref "U1") (pin "52") (pinfunction "VDD_52") (pintype "power_in"))
      (node (ref "U1") (pin "6") (pinfunction "VBAT_6") (pintype "power_in"))
      (node (ref "U1") (pin "62") (pinfunction "VDD_62") (pintype "power_in"))
      (node (ref "U1") (pin "72") (pinfunction "VDD_72") (pintype "power_in"))
      (node (ref "U1") (pin "84") (pinfunction "VDD_84") (pintype "power_in"))
      (node (ref "U1") (pin "95") (pinfunction "VDD_95") (pintype "power_in"))
    )
    (net (code "127") (name "unconnected-(P2-ID-Pad4)") (class "Default")
      (node (ref "P2") (pin "4") (pinfunction "ID_4") (pintype "passive+no_connect"))
    )
  )
)
